# LPCB235_-_CONTRAST_LASERS.net
KiCad netlist of a schematic drawn in Altium Designer
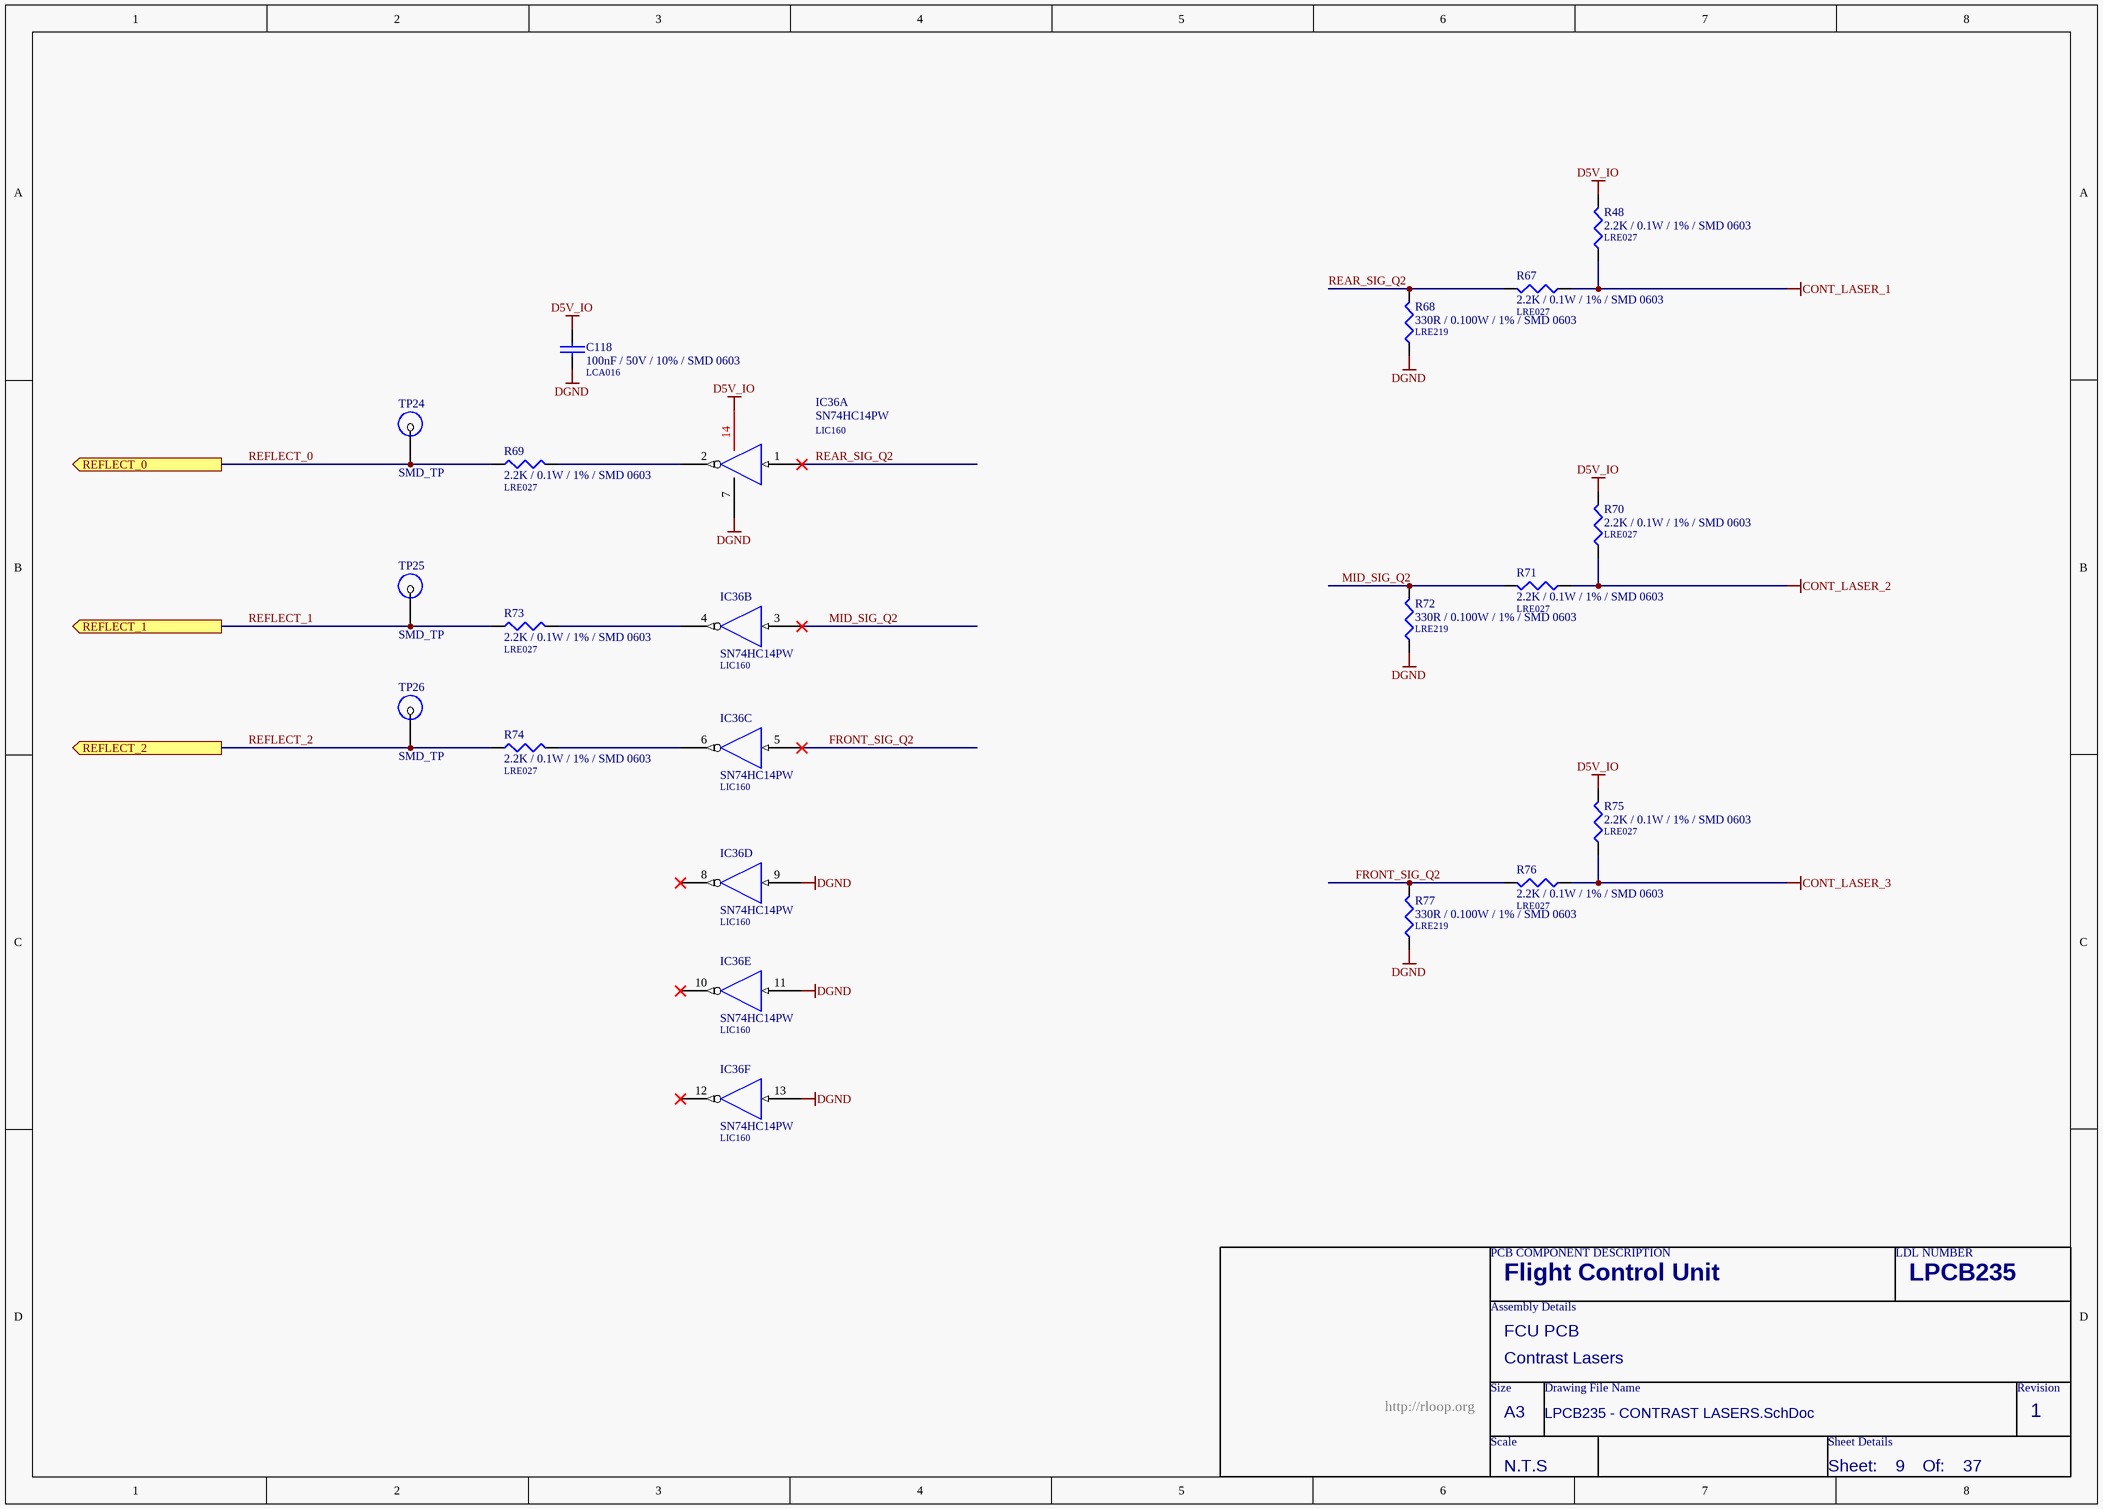
[diagram p0: LPCB235 - CONTRAST LASERS.SchDoc]

(export (version "E")
  (design (tool "Eeschema 10.0.6"))
  (components
    (comp (ref "C118")
      (value "100nF / 50V / 10% / SMD 0603")
      (footprint "LFP011__CC1608-0603-IPC7351_B")
      (description "Capacitor, Ceramic Chip, 100nF (0.1uF), 50V, 5%, SMD 0603 [LCA016]")
      (fields (field (name "LDL_NUMBER") "LCA016"))
      (libsource (lib "LDL_Capacitors") (part "100nF / 50V / 10% / SMD 0603"))
    )
    (comp (ref "IC36")
      (value "SN74HC14PW")
      (footprint "PW014")
      (description "IC, Hex Inveter, Schmitt Trigger, SMD [LIC160]")
      (fields (field (name "LDL_NUMBER") "LIC160"))
      (libsource (lib "LDL_Semiconductors") (part "SN74HC14PW"))
    )
    (comp (ref "R48")
      (value "2.2K / 0.1W / 1% / SMD 0603")
      (footprint "LFP020__CR1608-0603-IPC7351_B")
      (description "Resistor, Ceramic Chip, 2.2K, 0.1W, 1%, SMD 0603 [LRE027]")
      (fields (field (name "LDL_NUMBER") "LRE027"))
      (libsource (lib "LDL_Resistors") (part "2.2K / 0.1W / 1% / SMD 0603"))
    )
    (comp (ref "R67")
      (value "2.2K / 0.1W / 1% / SMD 0603")
      (footprint "LFP020__CR1608-0603-IPC7351_B")
      (description "Resistor, Ceramic Chip, 2.2K, 0.1W, 1%, SMD 0603 [LRE027]")
      (fields (field (name "LDL_NUMBER") "LRE027"))
      (libsource (lib "LDL_Resistors") (part "2.2K / 0.1W / 1% / SMD 0603"))
    )
    (comp (ref "R68")
      (value "330R / 0.100W / 1% / SMD 0603")
      (footprint "LFP020__CR1608-0603-IPC7351_B")
      (description "Resistor, Thick Film, 330R, 0.100W, 75V, 1%, SMD 0603 [LRE219]")
      (fields (field (name "LDL_NUMBER") "LRE219"))
      (libsource (lib "LDL_Resistors") (part "330R / 0.100W / 1% / SMD 0603"))
    )
    (comp (ref "R69")
      (value "2.2K / 0.1W / 1% / SMD 0603")
      (footprint "LFP020__CR1608-0603-IPC7351_B")
      (description "Resistor, Ceramic Chip, 2.2K, 0.1W, 1%, SMD 0603 [LRE027]")
      (fields (field (name "LDL_NUMBER") "LRE027"))
      (libsource (lib "LDL_Resistors") (part "2.2K / 0.1W / 1% / SMD 0603"))
    )
    (comp (ref "R70")
      (value "2.2K / 0.1W / 1% / SMD 0603")
      (footprint "LFP020__CR1608-0603-IPC7351_B")
      (description "Resistor, Ceramic Chip, 2.2K, 0.1W, 1%, SMD 0603 [LRE027]")
      (fields (field (name "LDL_NUMBER") "LRE027"))
      (libsource (lib "LDL_Resistors") (part "2.2K / 0.1W / 1% / SMD 0603"))
    )
    (comp (ref "R71")
      (value "2.2K / 0.1W / 1% / SMD 0603")
      (footprint "LFP020__CR1608-0603-IPC7351_B")
      (description "Resistor, Ceramic Chip, 2.2K, 0.1W, 1%, SMD 0603 [LRE027]")
      (fields (field (name "LDL_NUMBER") "LRE027"))
      (libsource (lib "LDL_Resistors") (part "2.2K / 0.1W / 1% / SMD 0603"))
    )
    (comp (ref "R72")
      (value "330R / 0.100W / 1% / SMD 0603")
      (footprint "LFP020__CR1608-0603-IPC7351_B")
      (description "Resistor, Thick Film, 330R, 0.100W, 75V, 1%, SMD 0603 [LRE219]")
      (fields (field (name "LDL_NUMBER") "LRE219"))
      (libsource (lib "LDL_Resistors") (part "330R / 0.100W / 1% / SMD 0603"))
    )
    (comp (ref "R73")
      (value "2.2K / 0.1W / 1% / SMD 0603")
      (footprint "LFP020__CR1608-0603-IPC7351_B")
      (description "Resistor, Ceramic Chip, 2.2K, 0.1W, 1%, SMD 0603 [LRE027]")
      (fields (field (name "LDL_NUMBER") "LRE027"))
      (libsource (lib "LDL_Resistors") (part "2.2K / 0.1W / 1% / SMD 0603"))
    )
    (comp (ref "R74")
      (value "2.2K / 0.1W / 1% / SMD 0603")
      (footprint "LFP020__CR1608-0603-IPC7351_B")
      (description "Resistor, Ceramic Chip, 2.2K, 0.1W, 1%, SMD 0603 [LRE027]")
      (fields (field (name "LDL_NUMBER") "LRE027"))
      (libsource (lib "LDL_Resistors") (part "2.2K / 0.1W / 1% / SMD 0603"))
    )
    (comp (ref "R75")
      (value "2.2K / 0.1W / 1% / SMD 0603")
      (footprint "LFP020__CR1608-0603-IPC7351_B")
      (description "Resistor, Ceramic Chip, 2.2K, 0.1W, 1%, SMD 0603 [LRE027]")
      (fields (field (name "LDL_NUMBER") "LRE027"))
      (libsource (lib "LDL_Resistors") (part "2.2K / 0.1W / 1% / SMD 0603"))
    )
    (comp (ref "R76")
      (value "2.2K / 0.1W / 1% / SMD 0603")
      (footprint "LFP020__CR1608-0603-IPC7351_B")
      (description "Resistor, Ceramic Chip, 2.2K, 0.1W, 1%, SMD 0603 [LRE027]")
      (fields (field (name "LDL_NUMBER") "LRE027"))
      (libsource (lib "LDL_Resistors") (part "2.2K / 0.1W / 1% / SMD 0603"))
    )
    (comp (ref "R77")
      (value "330R / 0.100W / 1% / SMD 0603")
      (footprint "LFP020__CR1608-0603-IPC7351_B")
      (description "Resistor, Thick Film, 330R, 0.100W, 75V, 1%, SMD 0603 [LRE219]")
      (fields (field (name "LDL_NUMBER") "LRE219"))
      (libsource (lib "LDL_Resistors") (part "330R / 0.100W / 1% / SMD 0603"))
    )
    (comp (ref "TP24")
      (value "SMD_TP")
      (footprint "SMD-TP")
      (description "SMD Test Point")
      (libsource (lib "LDL_Connectors") (part "SMD_TP"))
    )
    (comp (ref "TP25")
      (value "SMD_TP")
      (footprint "SMD-TP")
      (description "SMD Test Point")
      (libsource (lib "LDL_Connectors") (part "SMD_TP"))
    )
    (comp (ref "TP26")
      (value "SMD_TP")
      (footprint "SMD-TP")
      (description "SMD Test Point")
      (libsource (lib "LDL_Connectors") (part "SMD_TP"))
    )
  )
  (nets
    (net (code "1") (name "/FRONT_SIG_Q2") (class "Default")
      (node (ref "IC36") (pin "5") (pinfunction "A_5") (pintype "input"))
      (node (ref "R76") (pin "2") (pintype "passive"))
      (node (ref "R77") (pin "2") (pintype "passive"))
    )
    (net (code "2") (name "/MID_SIG_Q2") (class "Default")
      (node (ref "IC36") (pin "3") (pinfunction "A_3") (pintype "input"))
      (node (ref "R71") (pin "2") (pintype "passive"))
      (node (ref "R72") (pin "2") (pintype "passive"))
    )
    (net (code "3") (name "/REAR_SIG_Q2") (class "Default")
      (node (ref "IC36") (pin "1") (pinfunction "A_1") (pintype "input"))
      (node (ref "R67") (pin "2") (pintype "passive"))
      (node (ref "R68") (pin "2") (pintype "passive"))
    )
    (net (code "4") (name "/REFLECT_0") (class "Default")
      (node (ref "R69") (pin "1") (pintype "passive"))
      (node (ref "TP24") (pin "1") (pintype "passive"))
    )
    (net (code "5") (name "/REFLECT_1") (class "Default")
      (node (ref "R73") (pin "1") (pintype "passive"))
      (node (ref "TP25") (pin "1") (pintype "passive"))
    )
    (net (code "6") (name "/REFLECT_2") (class "Default")
      (node (ref "R74") (pin "1") (pintype "passive"))
      (node (ref "TP26") (pin "1") (pintype "passive"))
    )
    (net (code "7") (name "CONT_LASER_1") (class "Default")
      (node (ref "R48") (pin "1") (pintype "passive"))
      (node (ref "R67") (pin "1") (pintype "passive"))
    )
    (net (code "8") (name "CONT_LASER_2") (class "Default")
      (node (ref "R70") (pin "1") (pintype "passive"))
      (node (ref "R71") (pin "1") (pintype "passive"))
    )
    (net (code "9") (name "CONT_LASER_3") (class "Default")
      (node (ref "R75") (pin "1") (pintype "passive"))
      (node (ref "R76") (pin "1") (pintype "passive"))
    )
    (net (code "10") (name "D5V_IO") (class "Default")
      (node (ref "C118") (pin "1") (pintype "passive"))
      (node (ref "IC36") (pin "14") (pinfunction "VCC_14") (pintype "power_in"))
      (node (ref "R48") (pin "2") (pintype "passive"))
      (node (ref "R70") (pin "2") (pintype "passive"))
      (node (ref "R75") (pin "2") (pintype "passive"))
    )
    (net (code "11") (name "DGND") (class "Default")
      (node (ref "C118") (pin "2") (pintype "passive"))
      (node (ref "IC36") (pin "11") (pinfunction "A_11") (pintype "input"))
      (node (ref "IC36") (pin "13") (pinfunction "A_13") (pintype "input"))
      (node (ref "IC36") (pin "7") (pinfunction "GND_7") (pintype "power_in"))
      (node (ref "IC36") (pin "9") (pinfunction "A_9") (pintype "input"))
      (node (ref "R68") (pin "1") (pintype "passive"))
      (node (ref "R72") (pin "1") (pintype "passive"))
      (node (ref "R77") (pin "1") (pintype "passive"))
    )
    (net (code "12") (name "Net-(IC36A-Y)") (class "Default")
      (node (ref "IC36") (pin "2") (pinfunction "Y_2") (pintype "output"))
      (node (ref "R69") (pin "2") (pintype "passive"))
    )
    (net (code "13") (name "Net-(IC36B-Y)") (class "Default")
      (node (ref "IC36") (pin "4") (pinfunction "Y_4") (pintype "output"))
      (node (ref "R73") (pin "2") (pintype "passive"))
    )
    (net (code "14") (name "Net-(IC36C-Y)") (class "Default")
      (node (ref "IC36") (pin "6") (pinfunction "Y_6") (pintype "output"))
      (node (ref "R74") (pin "2") (pintype "passive"))
    )
    (net (code "15") (name "unconnected-(IC36D-Y-Pad8)") (class "Default")
      (node (ref "IC36") (pin "8") (pinfunction "Y_8") (pintype "output+no_connect"))
    )
    (net (code "16") (name "unconnected-(IC36E-Y-Pad10)") (class "Default")
      (node (ref "IC36") (pin "10") (pinfunction "Y_10") (pintype "output+no_connect"))
    )
    (net (code "17") (name "unconnected-(IC36F-Y-Pad12)") (class "Default")
      (node (ref "IC36") (pin "12") (pinfunction "Y_12") (pintype "output+no_connect"))
    )
  )
)
